# Timer_Ventilador_PIC.net
KiCad netlist of a schematic drawn in EAGLE
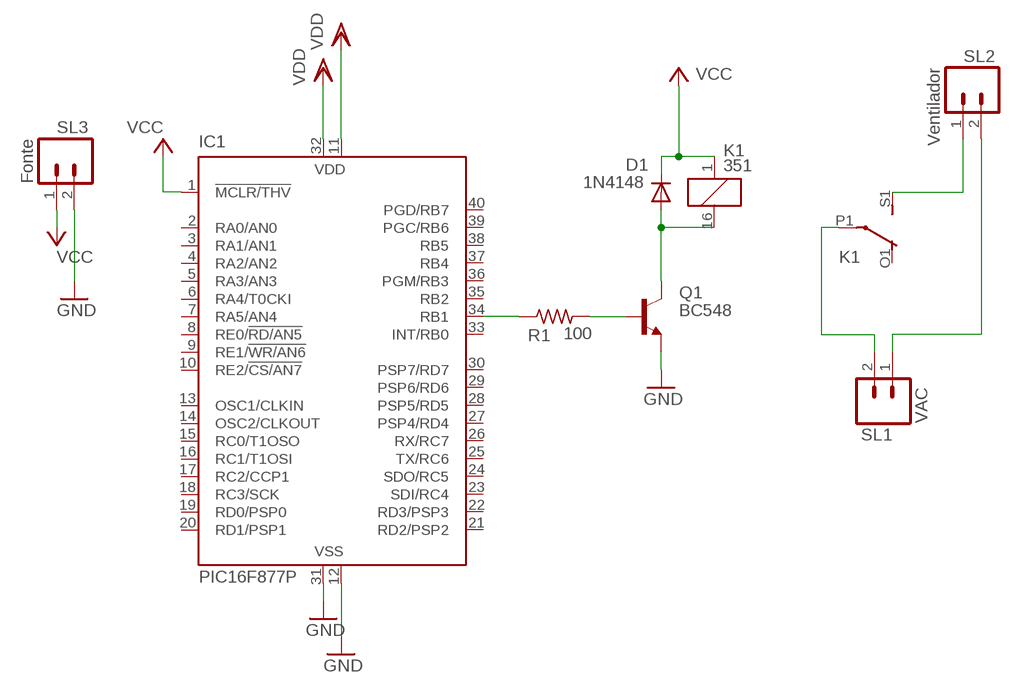
[diagram p0: schematic, sheet 1]

(export (version "E")
  (design (tool "Eeschema 10.0.6"))
  (components
    (comp (ref "D1")
      (value "1N4148")
      (footprint "eagle-import:DO35-7")
      (libsource (lib "eagle-import") (part "1N4148DO35-7"))
    )
    (comp (ref "IC1")
      (value "PIC16F877P")
      (footprint "eagle-import:DIL40")
      (fields (field (name "MF") "MICROCHIP") (field (name "MPN") "PIC16F877-04/P"))
      (libsource (lib "eagle-import") (part "PIC16F87P7"))
    )
    (comp (ref "K1")
      (value "351")
      (footprint "eagle-import:351")
      (libsource (lib "eagle-import") (part "351"))
    )
    (comp (ref "Q1")
      (value "BC548")
      (footprint "eagle-import:TO92-EBC")
      (libsource (lib "eagle-import") (part "BC548"))
    )
    (comp (ref "R1")
      (value "100")
      (footprint "eagle-import:0204_7")
      (libsource (lib "eagle-import") (part "R-US_0204/7"))
    )
    (comp (ref "SL1")
      (value "VAC")
      (footprint "eagle-import:02P")
      (libsource (lib "eagle-import") (part "M02"))
    )
    (comp (ref "SL2")
      (value "Ventilador")
      (footprint "eagle-import:02P")
      (libsource (lib "eagle-import") (part "M02"))
    )
    (comp (ref "SL3")
      (value "Fonte")
      (footprint "eagle-import:02P")
      (libsource (lib "eagle-import") (part "M02"))
    )
  )
  (nets
    (net (code "1") (name "GND") (class "Default")
      (node (ref "IC1") (pin "12") (pinfunction "VSS_12") (pintype "power_in"))
      (node (ref "IC1") (pin "31") (pinfunction "VSS_31") (pintype "power_in"))
      (node (ref "Q1") (pin "E") (pinfunction "E_E") (pintype "passive"))
      (node (ref "SL3") (pin "2") (pinfunction "2_2") (pintype "passive"))
    )
    (net (code "2") (name "Net-(IC1-RB1)") (class "Default")
      (node (ref "IC1") (pin "34") (pinfunction "RB1_34") (pintype "bidirectional"))
      (node (ref "R1") (pin "1") (pinfunction "1_1") (pintype "passive"))
    )
    (net (code "3") (name "Net-(K1A-2)") (class "Default")
      (node (ref "D1") (pin "A") (pinfunction "A_A") (pintype "passive"))
      (node (ref "K1") (pin "16") (pinfunction "2_16") (pintype "passive"))
      (node (ref "Q1") (pin "C") (pinfunction "C_C") (pintype "passive"))
    )
    (net (code "4") (name "Net-(K1B-P)") (class "Default")
      (node (ref "K1") (pin "P1") (pinfunction "P_P1") (pintype "passive"))
      (node (ref "SL1") (pin "2") (pinfunction "2_2") (pintype "passive"))
    )
    (net (code "5") (name "Net-(K1B-S)") (class "Default")
      (node (ref "K1") (pin "S1") (pinfunction "S_S1") (pintype "passive"))
      (node (ref "SL2") (pin "1") (pinfunction "1_1") (pintype "passive"))
    )
    (net (code "6") (name "Net-(Q1-PadB)") (class "Default")
      (node (ref "Q1") (pin "B") (pinfunction "B_B") (pintype "passive"))
      (node (ref "R1") (pin "2") (pinfunction "2_2") (pintype "passive"))
    )
    (net (code "7") (name "Net-(SL1-Pad1)") (class "Default")
      (node (ref "SL1") (pin "1") (pinfunction "1_1") (pintype "passive"))
      (node (ref "SL2") (pin "2") (pinfunction "2_2") (pintype "passive"))
    )
    (net (code "8") (name "VCC") (class "Default")
      (node (ref "D1") (pin "C") (pinfunction "C_C") (pintype "passive"))
      (node (ref "IC1") (pin "1") (pinfunction "~{MCLR/THV}_1") (pintype "input"))
      (node (ref "K1") (pin "1") (pinfunction "1_1") (pintype "passive"))
      (node (ref "SL3") (pin "1") (pinfunction "1_1") (pintype "passive"))
    )
    (net (code "9") (name "VDD") (class "Default")
      (node (ref "IC1") (pin "11") (pinfunction "VDD_11") (pintype "power_in"))
      (node (ref "IC1") (pin "32") (pinfunction "VDD_32") (pintype "power_in"))
    )
    (net (code "10") (name "unconnected-(IC1-INT{slash}RB0-Pad33)") (class "Default")
      (node (ref "IC1") (pin "33") (pinfunction "INT/RB0_33") (pintype "bidirectional"))
    )
    (net (code "11") (name "unconnected-(IC1-OSC1{slash}CLKIN-Pad13)") (class "Default")
      (node (ref "IC1") (pin "13") (pinfunction "OSC1/CLKIN_13") (pintype "input"))
    )
    (net (code "12") (name "unconnected-(IC1-OSC2{slash}CLKOUT-Pad14)") (class "Default")
      (node (ref "IC1") (pin "14") (pinfunction "OSC2/CLKOUT_14") (pintype "output"))
    )
    (net (code "13") (name "unconnected-(IC1-PGC{slash}RB6-Pad39)") (class "Default")
      (node (ref "IC1") (pin "39") (pinfunction "PGC/RB6_39") (pintype "bidirectional"))
    )
    (net (code "14") (name "unconnected-(IC1-PGD{slash}RB7-Pad40)") (class "Default")
      (node (ref "IC1") (pin "40") (pinfunction "PGD/RB7_40") (pintype "bidirectional"))
    )
    (net (code "15") (name "unconnected-(IC1-PGM{slash}RB3-Pad36)") (class "Default")
      (node (ref "IC1") (pin "36") (pinfunction "PGM/RB3_36") (pintype "bidirectional"))
    )
    (net (code "16") (name "unconnected-(IC1-PSP4{slash}RD4-Pad27)") (class "Default")
      (node (ref "IC1") (pin "27") (pinfunction "PSP4/RD4_27") (pintype "bidirectional"))
    )
    (net (code "17") (name "unconnected-(IC1-PSP5{slash}RD5-Pad28)") (class "Default")
      (node (ref "IC1") (pin "28") (pinfunction "PSP5/RD5_28") (pintype "bidirectional"))
    )
    (net (code "18") (name "unconnected-(IC1-PSP6{slash}RD6-Pad29)") (class "Default")
      (node (ref "IC1") (pin "29") (pinfunction "PSP6/RD6_29") (pintype "bidirectional"))
    )
    (net (code "19") (name "unconnected-(IC1-PSP7{slash}RD7-Pad30)") (class "Default")
      (node (ref "IC1") (pin "30") (pinfunction "PSP7/RD7_30") (pintype "bidirectional"))
    )
    (net (code "20") (name "unconnected-(IC1-RA0{slash}AN0-Pad2)") (class "Default")
      (node (ref "IC1") (pin "2") (pinfunction "RA0/AN0_2") (pintype "bidirectional"))
    )
    (net (code "21") (name "unconnected-(IC1-RA1{slash}AN1-Pad3)") (class "Default")
      (node (ref "IC1") (pin "3") (pinfunction "RA1/AN1_3") (pintype "bidirectional"))
    )
    (net (code "22") (name "unconnected-(IC1-RA2{slash}AN2-Pad4)") (class "Default")
      (node (ref "IC1") (pin "4") (pinfunction "RA2/AN2_4") (pintype "bidirectional"))
    )
    (net (code "23") (name "unconnected-(IC1-RA3{slash}AN3-Pad5)") (class "Default")
      (node (ref "IC1") (pin "5") (pinfunction "RA3/AN3_5") (pintype "bidirectional"))
    )
    (net (code "24") (name "unconnected-(IC1-RA4{slash}T0CKI-Pad6)") (class "Default")
      (node (ref "IC1") (pin "6") (pinfunction "RA4/T0CKI_6") (pintype "bidirectional"))
    )
    (net (code "25") (name "unconnected-(IC1-RA5{slash}AN4-Pad7)") (class "Default")
      (node (ref "IC1") (pin "7") (pinfunction "RA5/AN4_7") (pintype "bidirectional"))
    )
    (net (code "26") (name "unconnected-(IC1-RB2-Pad35)") (class "Default")
      (node (ref "IC1") (pin "35") (pinfunction "RB2_35") (pintype "bidirectional"))
    )
    (net (code "27") (name "unconnected-(IC1-RB4-Pad37)") (class "Default")
      (node (ref "IC1") (pin "37") (pinfunction "RB4_37") (pintype "bidirectional"))
    )
    (net (code "28") (name "unconnected-(IC1-RB5-Pad38)") (class "Default")
      (node (ref "IC1") (pin "38") (pinfunction "RB5_38") (pintype "bidirectional"))
    )
    (net (code "29") (name "unconnected-(IC1-RC0{slash}T1OSO-Pad15)") (class "Default")
      (node (ref "IC1") (pin "15") (pinfunction "RC0/T1OSO_15") (pintype "bidirectional"))
    )
    (net (code "30") (name "unconnected-(IC1-RC1{slash}T1OSI-Pad16)") (class "Default")
      (node (ref "IC1") (pin "16") (pinfunction "RC1/T1OSI_16") (pintype "bidirectional"))
    )
    (net (code "31") (name "unconnected-(IC1-RC2{slash}CCP1-Pad17)") (class "Default")
      (node (ref "IC1") (pin "17") (pinfunction "RC2/CCP1_17") (pintype "bidirectional"))
    )
    (net (code "32") (name "unconnected-(IC1-RC3{slash}SCK-Pad18)") (class "Default")
      (node (ref "IC1") (pin "18") (pinfunction "RC3/SCK_18") (pintype "bidirectional"))
    )
    (net (code "33") (name "unconnected-(IC1-RD0{slash}PSP0-Pad19)") (class "Default")
      (node (ref "IC1") (pin "19") (pinfunction "RD0/PSP0_19") (pintype "bidirectional"))
    )
    (net (code "34") (name "unconnected-(IC1-RD1{slash}PSP1-Pad20)") (class "Default")
      (node (ref "IC1") (pin "20") (pinfunction "RD1/PSP1_20") (pintype "bidirectional"))
    )
    (net (code "35") (name "unconnected-(IC1-RD2{slash}PSP2-Pad21)") (class "Default")
      (node (ref "IC1") (pin "21") (pinfunction "RD2/PSP2_21") (pintype "bidirectional"))
    )
    (net (code "36") (name "unconnected-(IC1-RD3{slash}PSP3-Pad22)") (class "Default")
      (node (ref "IC1") (pin "22") (pinfunction "RD3/PSP3_22") (pintype "bidirectional"))
    )
    (net (code "37") (name "unconnected-(IC1-RE0{slash}~{RD{slash}AN5}-Pad8)") (class "Default")
      (node (ref "IC1") (pin "8") (pinfunction "RE0/~{RD/AN5}_8") (pintype "bidirectional"))
    )
    (net (code "38") (name "unconnected-(IC1-RE1{slash}~{WR{slash}AN6}-Pad9)") (class "Default")
      (node (ref "IC1") (pin "9") (pinfunction "RE1/~{WR/AN6}_9") (pintype "bidirectional"))
    )
    (net (code "39") (name "unconnected-(IC1-RE2{slash}~{CS{slash}AN7}-Pad10)") (class "Default")
      (node (ref "IC1") (pin "10") (pinfunction "RE2/~{CS/AN7}_10") (pintype "bidirectional"))
    )
    (net (code "40") (name "unconnected-(IC1-RX{slash}RC7-Pad26)") (class "Default")
      (node (ref "IC1") (pin "26") (pinfunction "RX/RC7_26") (pintype "bidirectional"))
    )
    (net (code "41") (name "unconnected-(IC1-SDI{slash}RC4-Pad23)") (class "Default")
      (node (ref "IC1") (pin "23") (pinfunction "SDI/RC4_23") (pintype "bidirectional"))
    )
    (net (code "42") (name "unconnected-(IC1-SDO{slash}RC5-Pad24)") (class "Default")
      (node (ref "IC1") (pin "24") (pinfunction "SDO/RC5_24") (pintype "bidirectional"))
    )
    (net (code "43") (name "unconnected-(IC1-TX{slash}RC6-Pad25)") (class "Default")
      (node (ref "IC1") (pin "25") (pinfunction "TX/RC6_25") (pintype "bidirectional"))
    )
    (net (code "44") (name "unconnected-(K1B-O-PadO1)") (class "Default")
      (node (ref "K1") (pin "O1") (pinfunction "O_O1") (pintype "passive"))
    )
  )
)
